# UWB_F4_MCU.net
KiCad netlist of a schematic drawn in Altium Designer
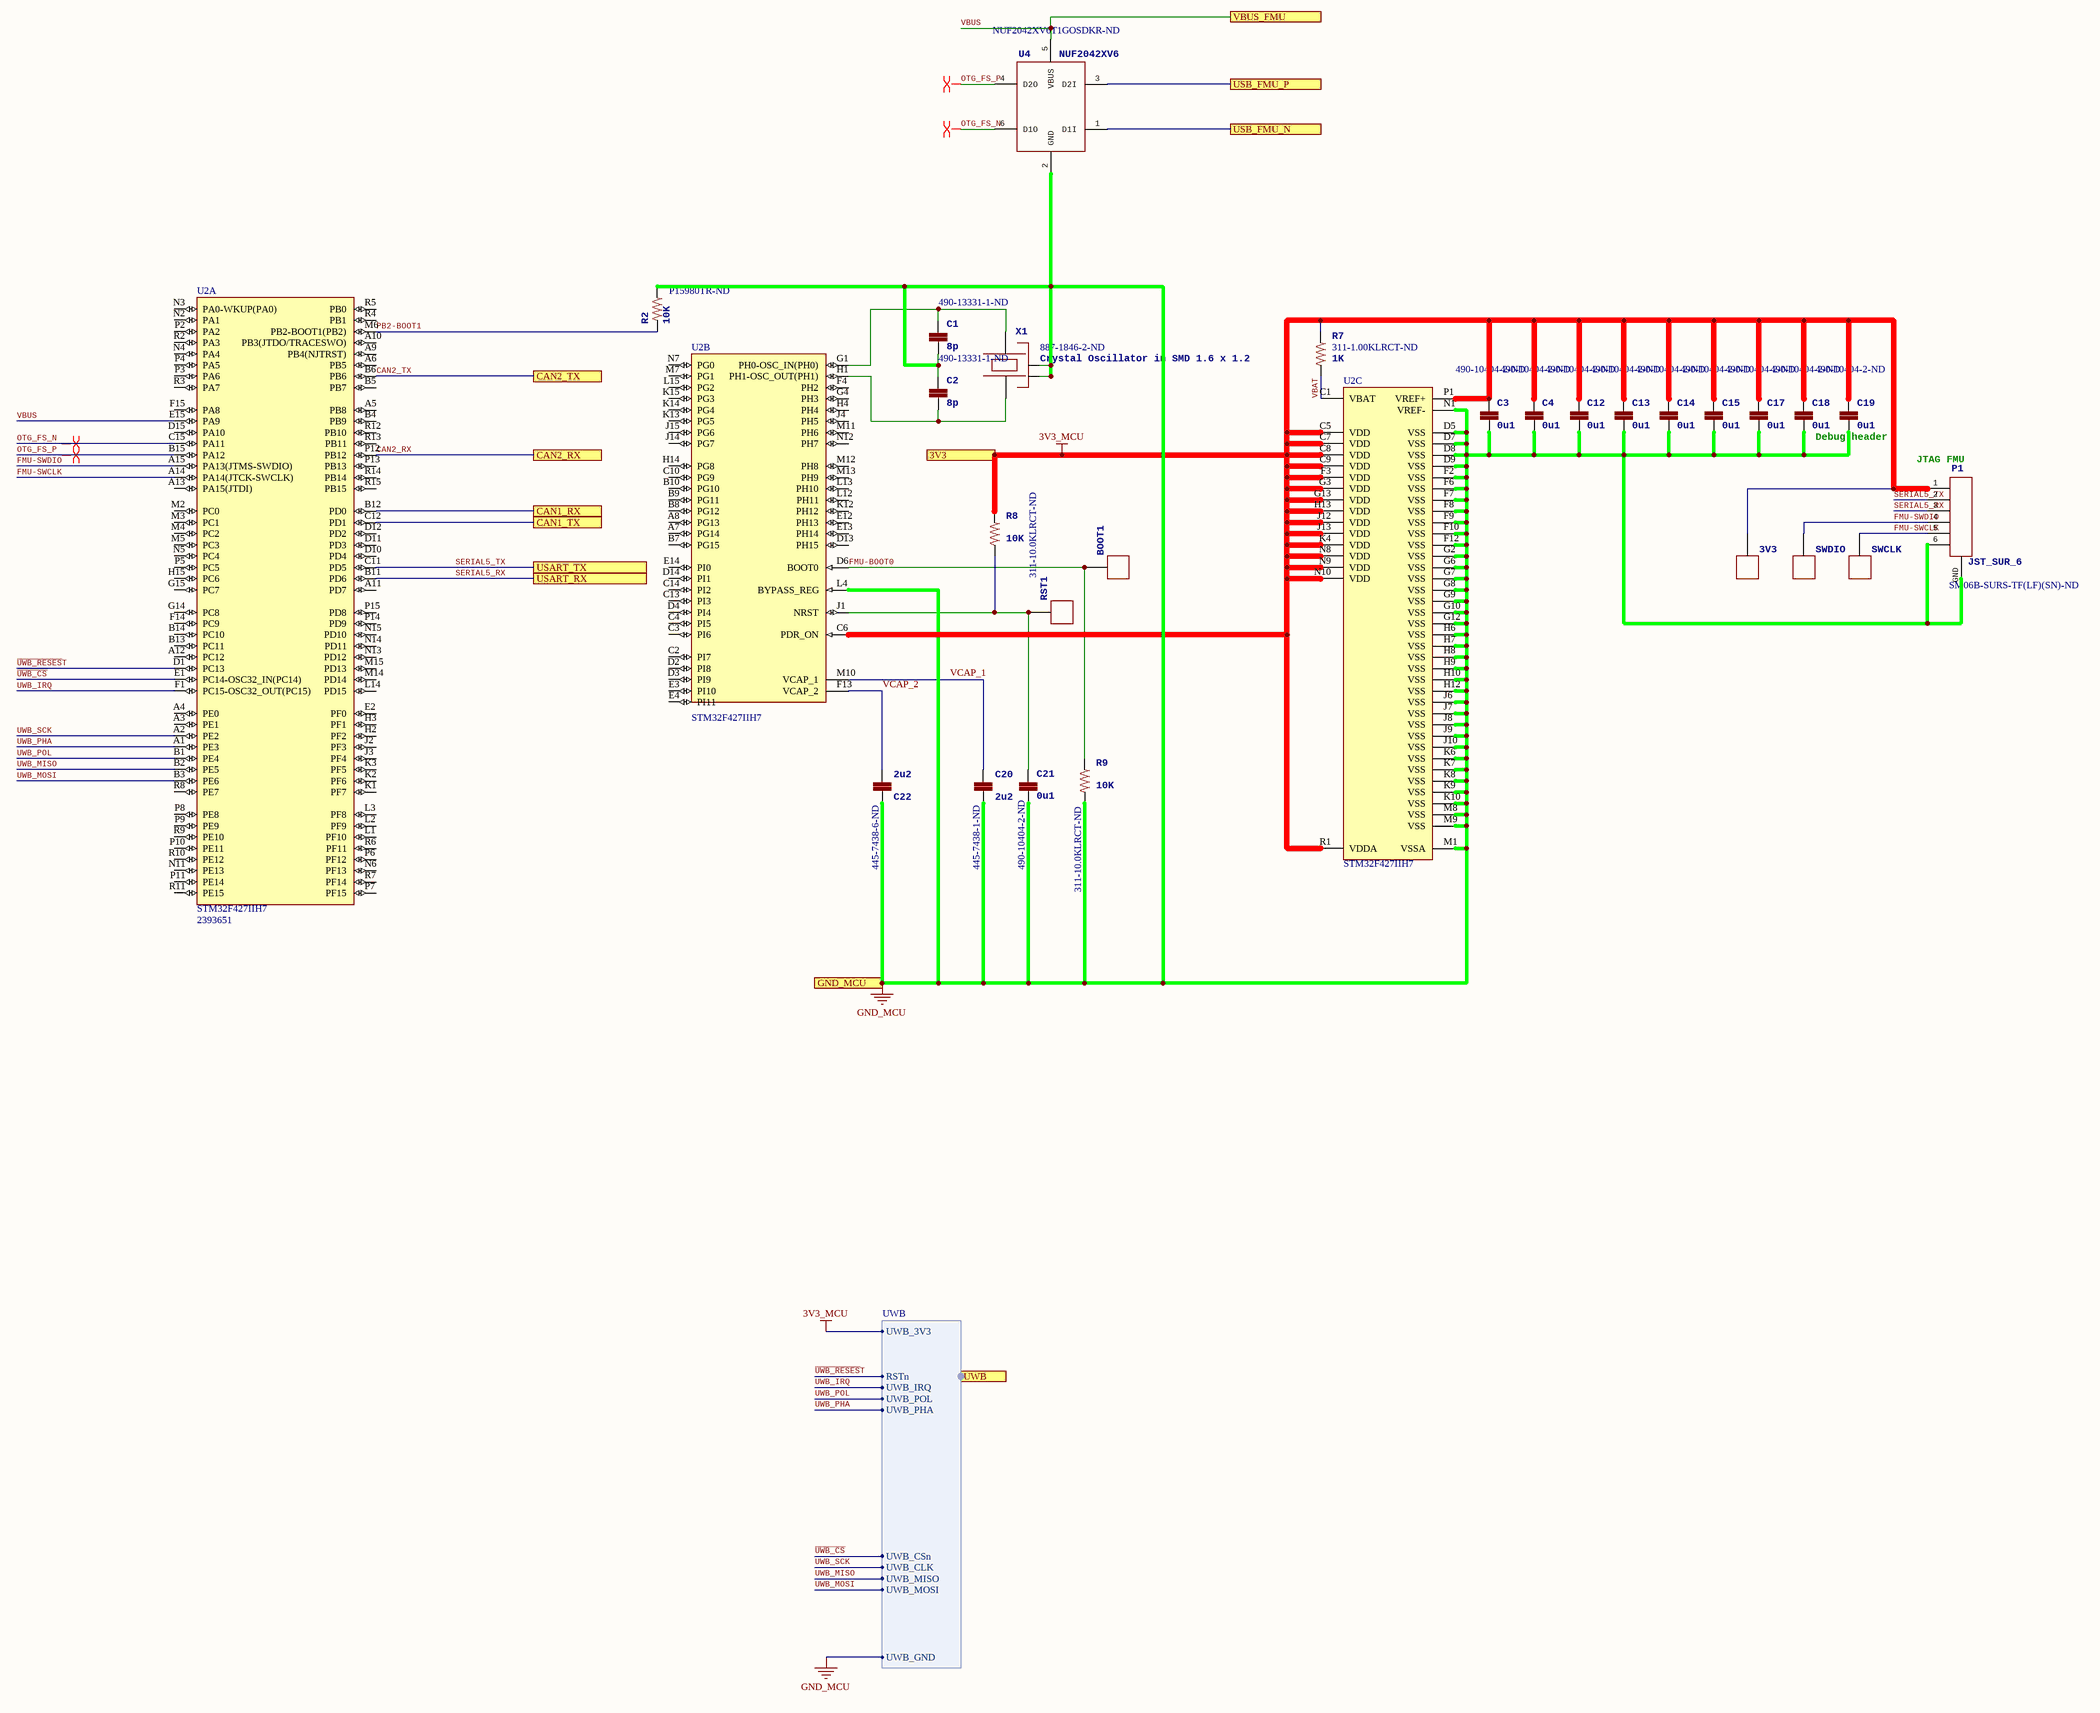
[diagram p0: UWB_F4_MCU.SchDoc]

(export (version "E")
  (design (tool "Eeschema 10.0.6"))
  (components
    (comp (ref "3V3") (value "~") (footprint "PAD.04X.04") (libsource (lib "pixhawk2") (part "PAD.04")))
    (comp (ref "BOOT1") (value "~") (footprint "PAD.04X.04") (libsource (lib "pixhawk2") (part "PAD.04")))
    (comp (ref "C1")
      (value "8p")
      (footprint "0201-cap")
      (description "CAP CER 8PF 50V NP0 0201")
      (fields (field (name "SUPPLIER PART NUMBER 1") "490-13331-1-ND"))
      (libsource (lib "altium-import") (part "root_0_CAP0402_"))
    )
    (comp (ref "C2")
      (value "8p")
      (footprint "0201-cap")
      (description "CAP CER 8PF 50V NP0 0201")
      (fields (field (name "SUPPLIER PART NUMBER 1") "490-13331-1-ND"))
      (libsource (lib "altium-import") (part "root_0_CAP0402_"))
    )
    (comp (ref "C3")
      (value "0u1")
      (footprint "0201-cap")
      (description "CAP CER 0.1UF 6V Y5V 0201")
      (fields (field (name "SUPPLIER PART NUMBER 1") "490-10404-2-ND"))
      (libsource (lib "altium-import") (part "root_0_CAP0402_"))
    )
    (comp (ref "C4")
      (value "0u1")
      (footprint "0201-cap")
      (description "CAP CER 0.1UF 6V Y5V 0201")
      (fields (field (name "SUPPLIER PART NUMBER 1") "490-10404-2-ND"))
      (libsource (lib "altium-import") (part "root_0_CAP0402_"))
    )
    (comp (ref "C12")
      (value "0u1")
      (footprint "0201-cap")
      (description "CAP CER 0.1UF 6V Y5V 0201")
      (fields (field (name "SUPPLIER PART NUMBER 1") "490-10404-2-ND"))
      (libsource (lib "altium-import") (part "root_0_CAP0402_"))
    )
    (comp (ref "C13")
      (value "0u1")
      (footprint "0201-cap")
      (description "CAP CER 0.1UF 6V Y5V 0201")
      (fields (field (name "SUPPLIER PART NUMBER 1") "490-10404-2-ND"))
      (libsource (lib "altium-import") (part "root_0_CAP0402_"))
    )
    (comp (ref "C14")
      (value "0u1")
      (footprint "0201-cap")
      (description "CAP CER 0.1UF 6V Y5V 0201")
      (fields (field (name "SUPPLIER PART NUMBER 1") "490-10404-2-ND"))
      (libsource (lib "altium-import") (part "root_0_CAP0402_"))
    )
    (comp (ref "C15")
      (value "0u1")
      (footprint "0201-cap")
      (description "CAP CER 0.1UF 6V Y5V 0201")
      (fields (field (name "SUPPLIER PART NUMBER 1") "490-10404-2-ND"))
      (libsource (lib "altium-import") (part "root_0_CAP0402_"))
    )
    (comp (ref "C17")
      (value "0u1")
      (footprint "0201-cap")
      (description "CAP CER 0.1UF 6V Y5V 0201")
      (fields (field (name "SUPPLIER PART NUMBER 1") "490-10404-2-ND"))
      (libsource (lib "altium-import") (part "root_0_CAP0402_"))
    )
    (comp (ref "C18")
      (value "0u1")
      (footprint "0201-cap")
      (description "CAP CER 0.1UF 6V Y5V 0201")
      (fields (field (name "SUPPLIER PART NUMBER 1") "490-10404-2-ND"))
      (libsource (lib "altium-import") (part "root_0_CAP0402_"))
    )
    (comp (ref "C19")
      (value "0u1")
      (footprint "0201-cap")
      (description "CAP CER 0.1UF 6V Y5V 0201")
      (fields (field (name "SUPPLIER PART NUMBER 1") "490-10404-2-ND"))
      (libsource (lib "altium-import") (part "root_0_CAP0402_"))
    )
    (comp (ref "C20")
      (value "2u2")
      (footprint "0603-CAP")
      (fields (field (name "SUPPLIER PART NUMBER 1") "445-7438-1-ND"))
      (libsource (lib "altium-import") (part "root_0_CAP0603_"))
    )
    (comp (ref "C21")
      (value "0u1")
      (footprint "0201-cap")
      (description "CAP CER 0.1UF 6V Y5V 0201")
      (fields (field (name "SUPPLIER PART NUMBER 1") "490-10404-2-ND"))
      (libsource (lib "altium-import") (part "root_0_CAP0402_"))
    )
    (comp (ref "C22")
      (value "2u2")
      (footprint "0603-CAP")
      (fields (field (name "SUPPLIER PART NUMBER 1") "445-7438-6-ND"))
      (libsource (lib "altium-import") (part "root_2_CAP0603_"))
    )
    (comp (ref "P1")
      (value "JST_SUR_6")
      (footprint "JST_SUR_H6")
      (description "Connector, Header, 6Pos, .8mm IDC, R/A, SMD, Tin")
      (fields (field (name "SUPPLIER PART NUMBER 1") "SM06B-SURS-TF(LF)(SN)-ND"))
      (libsource (lib "CB_SCI_AERO") (part "JST_SUR_6"))
    )
    (comp (ref "R2")
      (value "10K")
      (footprint "0201-RES")
      (description "RES 10K OHM 1% 0201 SMD")
      (fields (field (name "SUPPLIER PART NUMBER 1") "P15980TR-ND"))
      (libsource (lib "altium-import") (part "root_1_RESISTOR0402-RES_"))
    )
    (comp (ref "R7")
      (value "1K")
      (footprint "0402-RES")
      (fields (field (name "SUPPLIER PART NUMBER 1") "311-1.00KLRCT-ND"))
      (libsource (lib "altium-import") (part "root_1_RESISTOR0402-RES_"))
    )
    (comp (ref "R8")
      (value "10K")
      (footprint "0402-RES")
      (fields (field (name "SUPPLIER PART NUMBER 1") "311-10.0KLRCT-ND"))
      (libsource (lib "altium-import") (part "root_1_RESISTOR0402-RES_"))
    )
    (comp (ref "R9")
      (value "10K")
      (footprint "0402-RES")
      (fields (field (name "SUPPLIER PART NUMBER 1") "311-10.0KLRCT-ND"))
      (libsource (lib "altium-import") (part "root_1_RESISTOR0402-RES_"))
    )
    (comp (ref "RST1") (value "~") (footprint "PAD.04X.04") (libsource (lib "pixhawk2") (part "PAD.04")))
    (comp (ref "SWCLK") (value "~") (footprint "PAD.04X.04") (libsource (lib "pixhawk2") (part "PAD.04")))
    (comp (ref "SWDIO") (value "~") (footprint "PAD.04X.04") (libsource (lib "pixhawk2") (part "PAD.04")))
    (comp (ref "U2")
      (value "STM32F427IIH7")
      (footprint "STM-UFBGA176+25")
      (fields (field (name "SUPPLIER PART NUMBER 1") "2393651"))
      (libsource (lib "") (part "root_0_STM32F427IIH7__1"))
    )
    (comp (ref "U4")
      (value "NUF2042XV6")
      (footprint "SOT563-6")
      (description "IC FILTER USB ESD PROTECT SOT363")
      (fields (field (name "SUPPLIER PART NUMBER 1") "NUF2042XV6T1GOSDKR-ND"))
      (libsource (lib "altium-import") (part "root_0_NUF2042XV6_"))
    )
    (comp (ref "X1")
      (value "Crystal Oscillator in SMD 1.6 x 1.2")
      (footprint "OSCILLATOR-1.6x1.2")
      (description "CRYSTAL 24MHZ 8PF SMD")
      (fields (field (name "SUPPLIER PART NUMBER 1") "887-1846-2-ND"))
      (libsource (lib "altium-import") (part "root_0_OSCILLATOR-3.2X2.5_"))
    )
  )
  (nets
    (net (code "2") (name "/CAN1_RX") (class "Default")
      (node (ref "U2") (pin "B12") (pinfunction "PD0_B12") (pintype "bidirectional"))
    )
    (net (code "3") (name "/CAN1_TX") (class "Default")
      (node (ref "U2") (pin "C12") (pinfunction "PD1_C12") (pintype "bidirectional"))
    )
    (net (code "4") (name "/CAN2_RX") (class "Default")
      (node (ref "U2") (pin "P12") (pinfunction "PB12_P12") (pintype "bidirectional"))
    )
    (net (code "5") (name "/CAN2_TX") (class "Default")
      (node (ref "U2") (pin "B6") (pinfunction "PB6_B6") (pintype "bidirectional"))
    )
    (net (code "6") (name "/FMU-BOOT0") (class "Default")
      (node (ref "BOOT1") (pin "1") (pinfunction "1_1") (pintype "passive"))
      (node (ref "R9") (pin "2") (pinfunction "2_2") (pintype "passive"))
      (node (ref "U2") (pin "D6") (pinfunction "BOOT0_D6") (pintype "input"))
    )
    (net (code "7") (name "/FMU-SWCLK") (class "Default")
      (node (ref "P1") (pin "5") (pinfunction "5_5") (pintype "passive"))
      (node (ref "SWCLK") (pin "1") (pinfunction "1_1") (pintype "passive"))
      (node (ref "U2") (pin "A14") (pinfunction "PA14(JTCK-SWCLK)_A14") (pintype "bidirectional"))
    )
    (net (code "8") (name "/FMU-SWDIO") (class "Default")
      (node (ref "P1") (pin "4") (pinfunction "4_4") (pintype "passive"))
      (node (ref "SWDIO") (pin "1") (pinfunction "1_1") (pintype "passive"))
      (node (ref "U2") (pin "A15") (pinfunction "PA13(JTMS-SWDIO)_A15") (pintype "bidirectional"))
    )
    (net (code "9") (name "/OTG_FS_N") (class "Default")
      (node (ref "U2") (pin "C15") (pinfunction "PA11_C15") (pintype "bidirectional"))
      (node (ref "U4") (pin "6") (pinfunction "D1O_6") (pintype "passive"))
    )
    (net (code "10") (name "/OTG_FS_P") (class "Default")
      (node (ref "U2") (pin "B15") (pinfunction "PA12_B15") (pintype "bidirectional"))
      (node (ref "U4") (pin "4") (pinfunction "D2O_4") (pintype "passive"))
    )
    (net (code "11") (name "/PB2-BOOT1") (class "Default")
      (node (ref "R2") (pin "1") (pinfunction "1_1") (pintype "passive"))
      (node (ref "U2") (pin "M6") (pinfunction "PB2-BOOT1(PB2)_M6") (pintype "bidirectional"))
    )
    (net (code "12") (name "/SERIAL5_RX") (class "Default")
      (node (ref "P1") (pin "3") (pinfunction "3_3") (pintype "passive"))
      (node (ref "U2") (pin "B11") (pinfunction "PD6_B11") (pintype "bidirectional"))
    )
    (net (code "13") (name "/SERIAL5_TX") (class "Default")
      (node (ref "P1") (pin "2") (pinfunction "2_2") (pintype "passive"))
      (node (ref "U2") (pin "C11") (pinfunction "PD5_C11") (pintype "bidirectional"))
    )
    (net (code "14") (name "/USB_FMU_N") (class "Default")
      (node (ref "U4") (pin "1") (pinfunction "D1I_1") (pintype "passive"))
    )
    (net (code "15") (name "/USB_FMU_P") (class "Default")
      (node (ref "U4") (pin "3") (pinfunction "D2I_3") (pintype "passive"))
    )
    (net (code "16") (name "/UWB_IRQ") (class "Default")
      (node (ref "U2") (pin "F1") (pinfunction "PC15-OSC32_OUT(PC15)_F1") (pintype "bidirectional"))
    )
    (net (code "17") (name "/UWB_MISO") (class "Default")
      (node (ref "U2") (pin "B2") (pinfunction "PE5_B2") (pintype "bidirectional"))
    )
    (net (code "18") (name "/UWB_MOSI") (class "Default")
      (node (ref "U2") (pin "B3") (pinfunction "PE6_B3") (pintype "bidirectional"))
    )
    (net (code "19") (name "/UWB_PHA") (class "Default")
      (node (ref "U2") (pin "A1") (pinfunction "PE3_A1") (pintype "bidirectional"))
    )
    (net (code "20") (name "/UWB_POL") (class "Default")
      (node (ref "U2") (pin "B1") (pinfunction "PE4_B1") (pintype "bidirectional"))
    )
    (net (code "21") (name "/UWB_SCK") (class "Default")
      (node (ref "U2") (pin "A2") (pinfunction "PE2_A2") (pintype "bidirectional"))
    )
    (net (code "22") (name "/VBAT") (class "Default")
      (node (ref "R7") (pin "1") (pinfunction "1_1") (pintype "passive"))
      (node (ref "U2") (pin "C1") (pinfunction "VBAT_C1") (pintype "power_in"))
    )
    (net (code "23") (name "/VBUS") (class "Default")
      (node (ref "U2") (pin "E15") (pinfunction "PA9_E15") (pintype "bidirectional"))
      (node (ref "U4") (pin "5") (pinfunction "VBUS_5") (pintype "passive"))
    )
    (net (code "24") (name "/VCAP_1") (class "Default")
      (node (ref "C20") (pin "1") (pinfunction "1_1") (pintype "passive"))
      (node (ref "U2") (pin "M10") (pinfunction "VCAP_1_M10") (pintype "power_in"))
    )
    (net (code "25") (name "/VCAP_2") (class "Default")
      (node (ref "C22") (pin "2") (pinfunction "2_2") (pintype "passive"))
      (node (ref "U2") (pin "F13") (pinfunction "VCAP_2_F13") (pintype "power_in"))
    )
    (net (code "27") (name "/~{UWB_CS}") (class "Default")
      (node (ref "U2") (pin "E1") (pinfunction "PC14-OSC32_IN(PC14)_E1") (pintype "bidirectional"))
    )
    (net (code "28") (name "/~{UWB_RESES}T") (class "Default")
      (node (ref "U2") (pin "D1") (pinfunction "PC13_D1") (pintype "bidirectional"))
    )
    (net (code "29") (name "3V3_MCU") (class "Default")
      (node (ref "3V3") (pin "1") (pinfunction "1_1") (pintype "passive"))
      (node (ref "C12") (pin "1") (pinfunction "1_1") (pintype "passive"))
      (node (ref "C13") (pin "1") (pinfunction "1_1") (pintype "passive"))
      (node (ref "C14") (pin "1") (pinfunction "1_1") (pintype "passive"))
      (node (ref "C15") (pin "1") (pinfunction "1_1") (pintype "passive"))
      (node (ref "C17") (pin "1") (pinfunction "1_1") (pintype "passive"))
      (node (ref "C18") (pin "1") (pinfunction "1_1") (pintype "passive"))
      (node (ref "C19") (pin "1") (pinfunction "1_1") (pintype "passive"))
      (node (ref "C3") (pin "1") (pinfunction "1_1") (pintype "passive"))
      (node (ref "C4") (pin "1") (pinfunction "1_1") (pintype "passive"))
      (node (ref "P1") (pin "1") (pinfunction "1_1") (pintype "passive"))
      (node (ref "R7") (pin "2") (pinfunction "2_2") (pintype "passive"))
      (node (ref "R8") (pin "2") (pinfunction "2_2") (pintype "passive"))
      (node (ref "U2") (pin "C5") (pinfunction "VDD_C5") (pintype "power_in"))
      (node (ref "U2") (pin "C6") (pinfunction "PDR_ON_C6") (pintype "input"))
      (node (ref "U2") (pin "C7") (pinfunction "VDD_C7") (pintype "power_in"))
      (node (ref "U2") (pin "C8") (pinfunction "VDD_C8") (pintype "power_in"))
      (node (ref "U2") (pin "C9") (pinfunction "VDD_C9") (pintype "power_in"))
      (node (ref "U2") (pin "F3") (pinfunction "VDD_F3") (pintype "power_in"))
      (node (ref "U2") (pin "G13") (pinfunction "VDD_G13") (pintype "power_in"))
      (node (ref "U2") (pin "G3") (pinfunction "VDD_G3") (pintype "power_in"))
      (node (ref "U2") (pin "H13") (pinfunction "VDD_H13") (pintype "power_in"))
      (node (ref "U2") (pin "J12") (pinfunction "VDD_J12") (pintype "power_in"))
      (node (ref "U2") (pin "J13") (pinfunction "VDD_J13") (pintype "power_in"))
      (node (ref "U2") (pin "K4") (pinfunction "VDD_K4") (pintype "power_in"))
      (node (ref "U2") (pin "N10") (pinfunction "VDD_N10") (pintype "power_in"))
      (node (ref "U2") (pin "N8") (pinfunction "VDD_N8") (pintype "power_in"))
      (node (ref "U2") (pin "N9") (pinfunction "VDD_N9") (pintype "power_in"))
      (node (ref "U2") (pin "P1") (pinfunction "VREF+_P1") (pintype "power_in"))
      (node (ref "U2") (pin "R1") (pinfunction "VDDA_R1") (pintype "power_in"))
    )
    (net (code "30") (name "GND_MCU") (class "Default")
      (node (ref "C1") (pin "2") (pinfunction "2_2") (pintype "passive"))
      (node (ref "C12") (pin "2") (pinfunction "2_2") (pintype "passive"))
      (node (ref "C13") (pin "2") (pinfunction "2_2") (pintype "passive"))
      (node (ref "C14") (pin "2") (pinfunction "2_2") (pintype "passive"))
      (node (ref "C15") (pin "2") (pinfunction "2_2") (pintype "passive"))
      (node (ref "C17") (pin "2") (pinfunction "2_2") (pintype "passive"))
      (node (ref "C18") (pin "2") (pinfunction "2_2") (pintype "passive"))
      (node (ref "C19") (pin "2") (pinfunction "2_2") (pintype "passive"))
      (node (ref "C2") (pin "1") (pinfunction "1_1") (pintype "passive"))
      (node (ref "C20") (pin "2") (pinfunction "2_2") (pintype "passive"))
      (node (ref "C21") (pin "2") (pinfunction "2_2") (pintype "passive"))
      (node (ref "C22") (pin "1") (pinfunction "1_1") (pintype "passive"))
      (node (ref "C3") (pin "2") (pinfunction "2_2") (pintype "passive"))
      (node (ref "C4") (pin "2") (pinfunction "2_2") (pintype "passive"))
      (node (ref "P1") (pin "6") (pinfunction "6_6") (pintype "passive"))
      (node (ref "P1") (pin "GND") (pinfunction "GND_GND") (pintype "passive"))
      (node (ref "R2") (pin "2") (pinfunction "2_2") (pintype "passive"))
      (node (ref "R9") (pin "1") (pinfunction "1_1") (pintype "passive"))
      (node (ref "U2") (pin "D5") (pinfunction "VSS_D5") (pintype "power_in"))
      (node (ref "U2") (pin "D7") (pinfunction "VSS_D7") (pintype "power_in"))
      (node (ref "U2") (pin "D8") (pinfunction "VSS_D8") (pintype "power_in"))
      (node (ref "U2") (pin "D9") (pinfunction "VSS_D9") (pintype "power_in"))
      (node (ref "U2") (pin "F10") (pinfunction "VSS_F10") (pintype "power_in"))
      (node (ref "U2") (pin "F12") (pinfunction "VSS_F12") (pintype "power_in"))
      (node (ref "U2") (pin "F2") (pinfunction "VSS_F2") (pintype "power_in"))
      (node (ref "U2") (pin "F6") (pinfunction "VSS_F6") (pintype "power_in"))
      (node (ref "U2") (pin "F7") (pinfunction "VSS_F7") (pintype "power_in"))
      (node (ref "U2") (pin "F8") (pinfunction "VSS_F8") (pintype "power_in"))
      (node (ref "U2") (pin "F9") (pinfunction "VSS_F9") (pintype "power_in"))
      (node (ref "U2") (pin "G10") (pinfunction "VSS_G10") (pintype "power_in"))
      (node (ref "U2") (pin "G12") (pinfunction "VSS_G12") (pintype "power_in"))
      (node (ref "U2") (pin "G2") (pinfunction "VSS_G2") (pintype "power_in"))
      (node (ref "U2") (pin "G6") (pinfunction "VSS_G6") (pintype "power_in"))
      (node (ref "U2") (pin "G7") (pinfunction "VSS_G7") (pintype "power_in"))
      (node (ref "U2") (pin "G8") (pinfunction "VSS_G8") (pintype "power_in"))
      (node (ref "U2") (pin "G9") (pinfunction "VSS_G9") (pintype "power_in"))
      (node (ref "U2") (pin "H10") (pinfunction "VSS_H10") (pintype "power_in"))
      (node (ref "U2") (pin "H12") (pinfunction "VSS_H12") (pintype "power_in"))
      (node (ref "U2") (pin "H6") (pinfunction "VSS_H6") (pintype "power_in"))
      (node (ref "U2") (pin "H7") (pinfunction "VSS_H7") (pintype "power_in"))
      (node (ref "U2") (pin "H8") (pinfunction "VSS_H8") (pintype "power_in"))
      (node (ref "U2") (pin "H9") (pinfunction "VSS_H9") (pintype "power_in"))
      (node (ref "U2") (pin "J10") (pinfunction "VSS_J10") (pintype "power_in"))
      (node (ref "U2") (pin "J6") (pinfunction "VSS_J6") (pintype "power_in"))
      (node (ref "U2") (pin "J7") (pinfunction "VSS_J7") (pintype "power_in"))
      (node (ref "U2") (pin "J8") (pinfunction "VSS_J8") (pintype "power_in"))
      (node (ref "U2") (pin "J9") (pinfunction "VSS_J9") (pintype "power_in"))
      (node (ref "U2") (pin "K10") (pinfunction "VSS_K10") (pintype "power_in"))
      (node (ref "U2") (pin "K6") (pinfunction "VSS_K6") (pintype "power_in"))
      (node (ref "U2") (pin "K7") (pinfunction "VSS_K7") (pintype "power_in"))
      (node (ref "U2") (pin "K8") (pinfunction "VSS_K8") (pintype "power_in"))
      (node (ref "U2") (pin "K9") (pinfunction "VSS_K9") (pintype "power_in"))
      (node (ref "U2") (pin "L4") (pinfunction "BYPASS_REG_L4") (pintype "input"))
      (node (ref "U2") (pin "M1") (pinfunction "VSSA_M1") (pintype "power_in"))
      (node (ref "U2") (pin "M8") (pinfunction "VSS_M8") (pintype "power_in"))
      (node (ref "U2") (pin "M9") (pinfunction "VSS_M9") (pintype "power_in"))
      (node (ref "U2") (pin "N1") (pinfunction "VREF-_N1") (pintype "power_in"))
      (node (ref "U4") (pin "2") (pinfunction "GND_2") (pintype "passive"))
      (node (ref "X1") (pin "2") (pinfunction "NC_2_2") (pintype "passive"))
      (node (ref "X1") (pin "4") (pinfunction "NC_4_4") (pintype "passive"))
    )
    (net (code "31") (name "Net-(U2B-NRST)") (class "Default")
      (node (ref "C21") (pin "1") (pinfunction "1_1") (pintype "passive"))
      (node (ref "R8") (pin "1") (pinfunction "1_1") (pintype "passive"))
      (node (ref "RST1") (pin "1") (pinfunction "1_1") (pintype "passive"))
      (node (ref "U2") (pin "J1") (pinfunction "NRST_J1") (pintype "bidirectional"))
    )
    (net (code "32") (name "Net-(U2B-PH0-OSC_IN(PH0))") (class "Default")
      (node (ref "C1") (pin "1") (pinfunction "1_1") (pintype "passive"))
      (node (ref "U2") (pin "G1") (pinfunction "PH0-OSC_IN(PH0)_G1") (pintype "bidirectional"))
      (node (ref "X1") (pin "3") (pinfunction "3_3") (pintype "passive"))
    )
    (net (code "33") (name "Net-(U2B-PH1-OSC_OUT(PH1))") (class "Default")
      (node (ref "C2") (pin "2") (pinfunction "2_2") (pintype "passive"))
      (node (ref "U2") (pin "H1") (pinfunction "PH1-OSC_OUT(PH1)_H1") (pintype "bidirectional"))
      (node (ref "X1") (pin "1") (pinfunction "1_1") (pintype "passive"))
    )
    (net (code "34") (name "unconnected-(U2A-PA0-WKUP(PA0)-PadN3)") (class "Default")
      (node (ref "U2") (pin "N3") (pinfunction "PA0-WKUP(PA0)_N3") (pintype "bidirectional"))
    )
    (net (code "35") (name "unconnected-(U2A-PA1-PadN2)") (class "Default")
      (node (ref "U2") (pin "N2") (pinfunction "PA1_N2") (pintype "bidirectional"))
    )
    (net (code "36") (name "unconnected-(U2A-PA2-PadP2)") (class "Default")
      (node (ref "U2") (pin "P2") (pinfunction "PA2_P2") (pintype "bidirectional"))
    )
    (net (code "37") (name "unconnected-(U2A-PA3-PadR2)") (class "Default")
      (node (ref "U2") (pin "R2") (pinfunction "PA3_R2") (pintype "bidirectional"))
    )
    (net (code "38") (name "unconnected-(U2A-PA4-PadN4)") (class "Default")
      (node (ref "U2") (pin "N4") (pinfunction "PA4_N4") (pintype "bidirectional"))
    )
    (net (code "39") (name "unconnected-(U2A-PA5-PadP4)") (class "Default")
      (node (ref "U2") (pin "P4") (pinfunction "PA5_P4") (pintype "bidirectional"))
    )
    (net (code "40") (name "unconnected-(U2A-PA6-PadP3)") (class "Default")
      (node (ref "U2") (pin "P3") (pinfunction "PA6_P3") (pintype "bidirectional"))
    )
    (net (code "41") (name "unconnected-(U2A-PA7-PadR3)") (class "Default")
      (node (ref "U2") (pin "R3") (pinfunction "PA7_R3") (pintype "bidirectional"))
    )
    (net (code "42") (name "unconnected-(U2A-PA8-PadF15)") (class "Default")
      (node (ref "U2") (pin "F15") (pinfunction "PA8_F15") (pintype "bidirectional"))
    )
    (net (code "43") (name "unconnected-(U2A-PA10-PadD15)") (class "Default")
      (node (ref "U2") (pin "D15") (pinfunction "PA10_D15") (pintype "bidirectional"))
    )
    (net (code "44") (name "unconnected-(U2A-PA15(JTDI)-PadA13)") (class "Default")
      (node (ref "U2") (pin "A13") (pinfunction "PA15(JTDI)_A13") (pintype "bidirectional"))
    )
    (net (code "45") (name "unconnected-(U2A-PB0-PadR5)") (class "Default")
      (node (ref "U2") (pin "R5") (pinfunction "PB0_R5") (pintype "bidirectional"))
    )
    (net (code "46") (name "unconnected-(U2A-PB1-PadR4)") (class "Default")
      (node (ref "U2") (pin "R4") (pinfunction "PB1_R4") (pintype "bidirectional"))
    )
    (net (code "47") (name "unconnected-(U2A-PB3(JTDO{slash}TRACESWO)-PadA10)") (class "Default")
      (node (ref "U2") (pin "A10") (pinfunction "PB3(JTDO/TRACESWO)_A10") (pintype "bidirectional"))
    )
    (net (code "48") (name "unconnected-(U2A-PB4(NJTRST)-PadA9)") (class "Default")
      (node (ref "U2") (pin "A9") (pinfunction "PB4(NJTRST)_A9") (pintype "bidirectional"))
    )
    (net (code "49") (name "unconnected-(U2A-PB5-PadA6)") (class "Default")
      (node (ref "U2") (pin "A6") (pinfunction "PB5_A6") (pintype "bidirectional"))
    )
    (net (code "50") (name "unconnected-(U2A-PB7-PadB5)") (class "Default")
      (node (ref "U2") (pin "B5") (pinfunction "PB7_B5") (pintype "bidirectional"))
    )
    (net (code "51") (name "unconnected-(U2A-PB8-PadA5)") (class "Default")
      (node (ref "U2") (pin "A5") (pinfunction "PB8_A5") (pintype "bidirectional"))
    )
    (net (code "52") (name "unconnected-(U2A-PB9-PadB4)") (class "Default")
      (node (ref "U2") (pin "B4") (pinfunction "PB9_B4") (pintype "bidirectional"))
    )
    (net (code "53") (name "unconnected-(U2A-PB10-PadR12)") (class "Default")
      (node (ref "U2") (pin "R12") (pinfunction "PB10_R12") (pintype "bidirectional"))
    )
    (net (code "54") (name "unconnected-(U2A-PB11-PadR13)") (class "Default")
      (node (ref "U2") (pin "R13") (pinfunction "PB11_R13") (pintype "bidirectional"))
    )
    (net (code "55") (name "unconnected-(U2A-PB13-PadP13)") (class "Default")
      (node (ref "U2") (pin "P13") (pinfunction "PB13_P13") (pintype "bidirectional"))
    )
    (net (code "56") (name "unconnected-(U2A-PB14-PadR14)") (class "Default")
      (node (ref "U2") (pin "R14") (pinfunction "PB14_R14") (pintype "bidirectional"))
    )
    (net (code "57") (name "unconnected-(U2A-PB15-PadR15)") (class "Default")
      (node (ref "U2") (pin "R15") (pinfunction "PB15_R15") (pintype "bidirectional"))
    )
    (net (code "58") (name "unconnected-(U2A-PC0-PadM2)") (class "Default")
      (node (ref "U2") (pin "M2") (pinfunction "PC0_M2") (pintype "bidirectional"))
    )
    (net (code "59") (name "unconnected-(U2A-PC1-PadM3)") (class "Default")
      (node (ref "U2") (pin "M3") (pinfunction "PC1_M3") (pintype "bidirectional"))
    )
    (net (code "60") (name "unconnected-(U2A-PC2-PadM4)") (class "Default")
      (node (ref "U2") (pin "M4") (pinfunction "PC2_M4") (pintype "bidirectional"))
    )
    (net (code "61") (name "unconnected-(U2A-PC3-PadM5)") (class "Default")
      (node (ref "U2") (pin "M5") (pinfunction "PC3_M5") (pintype "bidirectional"))
    )
    (net (code "62") (name "unconnected-(U2A-PC4-PadN5)") (class "Default")
      (node (ref "U2") (pin "N5") (pinfunction "PC4_N5") (pintype "bidirectional"))
    )
    (net (code "63") (name "unconnected-(U2A-PC5-PadP5)") (class "Default")
      (node (ref "U2") (pin "P5") (pinfunction "PC5_P5") (pintype "bidirectional"))
    )
    (net (code "64") (name "unconnected-(U2A-PC6-PadH15)") (class "Default")
      (node (ref "U2") (pin "H15") (pinfunction "PC6_H15") (pintype "bidirectional"))
    )
    (net (code "65") (name "unconnected-(U2A-PC7-PadG15)") (class "Default")
      (node (ref "U2") (pin "G15") (pinfunction "PC7_G15") (pintype "bidirectional"))
    )
    (net (code "66") (name "unconnected-(U2A-PC8-PadG14)") (class "Default")
      (node (ref "U2") (pin "G14") (pinfunction "PC8_G14") (pintype "bidirectional"))
    )
    (net (code "67") (name "unconnected-(U2A-PC9-PadF14)") (class "Default")
      (node (ref "U2") (pin "F14") (pinfunction "PC9_F14") (pintype "bidirectional"))
    )
    (net (code "68") (name "unconnected-(U2A-PC10-PadB14)") (class "Default")
      (node (ref "U2") (pin "B14") (pinfunction "PC10_B14") (pintype "bidirectional"))
    )
    (net (code "69") (name "unconnected-(U2A-PC11-PadB13)") (class "Default")
      (node (ref "U2") (pin "B13") (pinfunction "PC11_B13") (pintype "bidirectional"))
    )
    (net (code "70") (name "unconnected-(U2A-PC12-PadA12)") (class "Default")
      (node (ref "U2") (pin "A12") (pinfunction "PC12_A12") (pintype "bidirectional"))
    )
    (net (code "71") (name "unconnected-(U2A-PD2-PadD12)") (class "Default")
      (node (ref "U2") (pin "D12") (pinfunction "PD2_D12") (pintype "bidirectional"))
    )
    (net (code "72") (name "unconnected-(U2A-PD3-PadD11)") (class "Default")
      (node (ref "U2") (pin "D11") (pinfunction "PD3_D11") (pintype "bidirectional"))
    )
    (net (code "73") (name "unconnected-(U2A-PD4-PadD10)") (class "Default")
      (node (ref "U2") (pin "D10") (pinfunction "PD4_D10") (pintype "bidirectional"))
    )
    (net (code "74") (name "unconnected-(U2A-PD7-PadA11)") (class "Default")
      (node (ref "U2") (pin "A11") (pinfunction "PD7_A11") (pintype "bidirectional"))
    )
    (net (code "75") (name "unconnected-(U2A-PD8-PadP15)") (class "Default")
      (node (ref "U2") (pin "P15") (pinfunction "PD8_P15") (pintype "bidirectional"))
    )
    (net (code "76") (name "unconnected-(U2A-PD9-PadP14)") (class "Default")
      (node (ref "U2") (pin "P14") (pinfunction "PD9_P14") (pintype "bidirectional"))
    )
    (net (code "77") (name "unconnected-(U2A-PD10-PadN15)") (class "Default")
      (node (ref "U2") (pin "N15") (pinfunction "PD10_N15") (pintype "bidirectional"))
    )
    (net (code "78") (name "unconnected-(U2A-PD11-PadN14)") (class "Default")
      (node (ref "U2") (pin "N14") (pinfunction "PD11_N14") (pintype "bidirectional"))
    )
    (net (code "79") (name "unconnected-(U2A-PD12-PadN13)") (class "Default")
      (node (ref "U2") (pin "N13") (pinfunction "PD12_N13") (pintype "bidirectional"))
    )
    (net (code "80") (name "unconnected-(U2A-PD13-PadM15)") (class "Default")
      (node (ref "U2") (pin "M15") (pinfunction "PD13_M15") (pintype "bidirectional"))
    )
    (net (code "81") (name "unconnected-(U2A-PD14-PadM14)") (class "Default")
      (node (ref "U2") (pin "M14") (pinfunction "PD14_M14") (pintype "bidirectional"))
    )
    (net (code "82") (name "unconnected-(U2A-PD15-PadL14)") (class "Default")
      (node (ref "U2") (pin "L14") (pinfunction "PD15_L14") (pintype "bidirectional"))
    )
    (net (code "83") (name "unconnected-(U2A-PE0-PadA4)") (class "Default")
      (node (ref "U2") (pin "A4") (pinfunction "PE0_A4") (pintype "bidirectional"))
    )
    (net (code "84") (name "unconnected-(U2A-PE1-PadA3)") (class "Default")
      (node (ref "U2") (pin "A3") (pinfunction "PE1_A3") (pintype "bidirectional"))
    )
    (net (code "85") (name "unconnected-(U2A-PE7-PadR8)") (class "Default")
      (node (ref "U2") (pin "R8") (pinfunction "PE7_R8") (pintype "bidirectional"))
    )
    (net (code "86") (name "unconnected-(U2A-PE8-PadP8)") (class "Default")
      (node (ref "U2") (pin "P8") (pinfunction "PE8_P8") (pintype "bidirectional"))
    )
    (net (code "87") (name "unconnected-(U2A-PE9-PadP9)") (class "Default")
      (node (ref "U2") (pin "P9") (pinfunction "PE9_P9") (pintype "bidirectional"))
    )
    (net (code "88") (name "unconnected-(U2A-PE10-PadR9)") (class "Default")
      (node (ref "U2") (pin "R9") (pinfunction "PE10_R9") (pintype "bidirectional"))
    )
    (net (code "89") (name "unconnected-(U2A-PE11-PadP10)") (class "Default")
      (node (ref "U2") (pin "P10") (pinfunction "PE11_P10") (pintype "bidirectional"))
    )
    (net (code "90") (name "unconnected-(U2A-PE12-PadR10)") (class "Default")
      (node (ref "U2") (pin "R10") (pinfunction "PE12_R10") (pintype "bidirectional"))
    )
    (net (code "91") (name "unconnected-(U2A-PE13-PadN11)") (class "Default")
      (node (ref "U2") (pin "N11") (pinfunction "PE13_N11") (pintype "bidirectional"))
    )
    (net (code "92") (name "unconnected-(U2A-PE14-PadP11)") (class "Default")
      (node (ref "U2") (pin "P11") (pinfunction "PE14_P11") (pintype "bidirectional"))
    )
    (net (code "93") (name "unconnected-(U2A-PE15-PadR11)") (class "Default")
      (node (ref "U2") (pin "R11") (pinfunction "PE15_R11") (pintype "bidirectional"))
    )
    (net (code "94") (name "unconnected-(U2A-PF0-PadE2)") (class "Default")
      (node (ref "U2") (pin "E2") (pinfunction "PF0_E2") (pintype "bidirectional"))
    )
    (net (code "95") (name "unconnected-(U2A-PF1-PadH3)") (class "Default")
      (node (ref "U2") (pin "H3") (pinfunction "PF1_H3") (pintype "bidirectional"))
    )
    (net (code "96") (name "unconnected-(U2A-PF2-PadH2)") (class "Default")
      (node (ref "U2") (pin "H2") (pinfunction "PF2_H2") (pintype "bidirectional"))
    )
    (net (code "97") (name "unconnected-(U2A-PF3-PadJ2)") (class "Default")
      (node (ref "U2") (pin "J2") (pinfunction "PF3_J2") (pintype "bidirectional"))
    )
    (net (code "98") (name "unconnected-(U2A-PF4-PadJ3)") (class "Default")
      (node (ref "U2") (pin "J3") (pinfunction "PF4_J3") (pintype "bidirectional"))
    )
    (net (code "99") (name "unconnected-(U2A-PF5-PadK3)") (class "Default")
      (node (ref "U2") (pin "K3") (pinfunction "PF5_K3") (pintype "bidirectional"))
    )
    (net (code "100") (name "unconnected-(U2A-PF6-PadK2)") (class "Default")
      (node (ref "U2") (pin "K2") (pinfunction "PF6_K2") (pintype "bidirectional"))
    )
    (net (code "101") (name "unconnected-(U2A-PF7-PadK1)") (class "Default")
      (node (ref "U2") (pin "K1") (pinfunction "PF7_K1") (pintype "bidirectional"))
    )
    (net (code "102") (name "unconnected-(U2A-PF8-PadL3)") (class "Default")
      (node (ref "U2") (pin "L3") (pinfunction "PF8_L3") (pintype "bidirectional"))
    )
    (net (code "103") (name "unconnected-(U2A-PF9-PadL2)") (class "Default")
      (node (ref "U2") (pin "L2") (pinfunction "PF9_L2") (pintype "bidirectional"))
    )
    (net (code "104") (name "unconnected-(U2A-PF10-PadL1)") (class "Default")
      (node (ref "U2") (pin "L1") (pinfunction "PF10_L1") (pintype "bidirectional"))
    )
    (net (code "105") (name "unconnected-(U2A-PF11-PadR6)") (class "Default")
      (node (ref "U2") (pin "R6") (pinfunction "PF11_R6") (pintype "bidirectional"))
    )
    (net (code "106") (name "unconnected-(U2A-PF12-PadP6)") (class "Default")
      (node (ref "U2") (pin "P6") (pinfunction "PF12_P6") (pintype "bidirectional"))
    )
    (net (code "107") (name "unconnected-(U2A-PF13-PadN6)") (class "Default")
      (node (ref "U2") (pin "N6") (pinfunction "PF13_N6") (pintype "bidirectional"))
    )
    (net (code "108") (name "unconnected-(U2A-PF14-PadR7)") (class "Default")
      (node (ref "U2") (pin "R7") (pinfunction "PF14_R7") (pintype "bidirectional"))
    )
    (net (code "109") (name "unconnected-(U2A-PF15-PadP7)") (class "Default")
      (node (ref "U2") (pin "P7") (pinfunction "PF15_P7") (pintype "bidirectional"))
    )
    (net (code "110") (name "unconnected-(U2B-PG0-PadN7)") (class "Default")
      (node (ref "U2") (pin "N7") (pinfunction "PG0_N7") (pintype "bidirectional"))
    )
    (net (code "111") (name "unconnected-(U2B-PG1-PadM7)") (class "Default")
      (node (ref "U2") (pin "M7") (pinfunction "PG1_M7") (pintype "bidirectional"))
    )
    (net (code "112") (name "unconnected-(U2B-PG2-PadL15)") (class "Default")
      (node (ref "U2") (pin "L15") (pinfunction "PG2_L15") (pintype "bidirectional"))
    )
    (net (code "113") (name "unconnected-(U2B-PG3-PadK15)") (class "Default")
      (node (ref "U2") (pin "K15") (pinfunction "PG3_K15") (pintype "bidirectional"))
    )
    (net (code "114") (name "unconnected-(U2B-PG4-PadK14)") (class "Default")
      (node (ref "U2") (pin "K14") (pinfunction "PG4_K14") (pintype "bidirectional"))
    )
    (net (code "115") (name "unconnected-(U2B-PG5-PadK13)") (class "Default")
      (node (ref "U2") (pin "K13") (pinfunction "PG5_K13") (pintype "bidirectional"))
    )
    (net (code "116") (name "unconnected-(U2B-PG6-PadJ15)") (class "Default")
      (node (ref "U2") (pin "J15") (pinfunction "PG6_J15") (pintype "bidirectional"))
    )
    (net (code "117") (name "unconnected-(U2B-PG7-PadJ14)") (class "Default")
      (node (ref "U2") (pin "J14") (pinfunction "PG7_J14") (pintype "bidirectional"))
    )
    (net (code "118") (name "unconnected-(U2B-PG8-PadH14)") (class "Default")
      (node (ref "U2") (pin "H14") (pinfunction "PG8_H14") (pintype "bidirectional"))
    )
    (net (code "119") (name "unconnected-(U2B-PG9-PadC10)") (class "Default")
      (node (ref "U2") (pin "C10") (pinfunction "PG9_C10") (pintype "bidirectional"))
    )
    (net (code "120") (name "unconnected-(U2B-PG10-PadB10)") (class "Default")
      (node (ref "U2") (pin "B10") (pinfunction "PG10_B10") (pintype "bidirectional"))
    )
    (net (code "121") (name "unconnected-(U2B-PG11-PadB9)") (class "Default")
      (node (ref "U2") (pin "B9") (pinfunction "PG11_B9") (pintype "bidirectional"))
    )
    (net (code "122") (name "unconnected-(U2B-PG12-PadB8)") (class "Default")
      (node (ref "U2") (pin "B8") (pinfunction "PG12_B8") (pintype "bidirectional"))
    )
    (net (code "123") (name "unconnected-(U2B-PG13-PadA8)") (class "Default")
      (node (ref "U2") (pin "A8") (pinfunction "PG13_A8") (pintype "bidirectional"))
    )
    (net (code "124") (name "unconnected-(U2B-PG14-PadA7)") (class "Default")
      (node (ref "U2") (pin "A7") (pinfunction "PG14_A7") (pintype "bidirectional"))
    )
    (net (code "125") (name "unconnected-(U2B-PG15-PadB7)") (class "Default")
      (node (ref "U2") (pin "B7") (pinfunction "PG15_B7") (pintype "bidirectional"))
    )
    (net (code "126") (name "unconnected-(U2B-PH2-PadF4)") (class "Default")
      (node (ref "U2") (pin "F4") (pinfunction "PH2_F4") (pintype "bidirectional"))
    )
    (net (code "127") (name "unconnected-(U2B-PH3-PadG4)") (class "Default")
      (node (ref "U2") (pin "G4") (pinfunction "PH3_G4") (pintype "bidirectional"))
    )
    (net (code "128") (name "unconnected-(U2B-PH4-PadH4)") (class "Default")
      (node (ref "U2") (pin "H4") (pinfunction "PH4_H4") (pintype "bidirectional"))
    )
    (net (code "129") (name "unconnected-(U2B-PH5-PadJ4)") (class "Default")
      (node (ref "U2") (pin "J4") (pinfunction "PH5_J4") (pintype "bidirectional"))
    )
    (net (code "130") (name "unconnected-(U2B-PH6-PadM11)") (class "Default")
      (node (ref "U2") (pin "M11") (pinfunction "PH6_M11") (pintype "bidirectional"))
    )
    (net (code "131") (name "unconnected-(U2B-PH7-PadN12)") (class "Default")
      (node (ref "U2") (pin "N12") (pinfunction "PH7_N12") (pintype "bidirectional"))
    )
    (net (code "132") (name "unconnected-(U2B-PH8-PadM12)") (class "Default")
      (node (ref "U2") (pin "M12") (pinfunction "PH8_M12") (pintype "bidirectional"))
    )
    (net (code "133") (name "unconnected-(U2B-PH9-PadM13)") (class "Default")
      (node (ref "U2") (pin "M13") (pinfunction "PH9_M13") (pintype "bidirectional"))
    )
    (net (code "134") (name "unconnected-(U2B-PH10-PadL13)") (class "Default")
      (node (ref "U2") (pin "L13") (pinfunction "PH10_L13") (pintype "bidirectional"))
    )
    (net (code "135") (name "unconnected-(U2B-PH11-PadL12)") (class "Default")
      (node (ref "U2") (pin "L12") (pinfunction "PH11_L12") (pintype "bidirectional"))
    )
    (net (code "136") (name "unconnected-(U2B-PH12-PadK12)") (class "Default")
      (node (ref "U2") (pin "K12") (pinfunction "PH12_K12") (pintype "bidirectional"))
    )
    (net (code "137") (name "unconnected-(U2B-PH13-PadE12)") (class "Default")
      (node (ref "U2") (pin "E12") (pinfunction "PH13_E12") (pintype "bidirectional"))
    )
    (net (code "138") (name "unconnected-(U2B-PH14-PadE13)") (class "Default")
      (node (ref "U2") (pin "E13") (pinfunction "PH14_E13") (pintype "bidirectional"))
    )
    (net (code "139") (name "unconnected-(U2B-PH15-PadD13)") (class "Default")
      (node (ref "U2") (pin "D13") (pinfunction "PH15_D13") (pintype "bidirectional"))
    )
    (net (code "140") (name "unconnected-(U2B-PI0-PadE14)") (class "Default")
      (node (ref "U2") (pin "E14") (pinfunction "PI0_E14") (pintype "bidirectional"))
    )
    (net (code "141") (name "unconnected-(U2B-PI1-PadD14)") (class "Default")
      (node (ref "U2") (pin "D14") (pinfunction "PI1_D14") (pintype "bidirectional"))
    )
    (net (code "142") (name "unconnected-(U2B-PI2-PadC14)") (class "Default")
      (node (ref "U2") (pin "C14") (pinfunction "PI2_C14") (pintype "bidirectional"))
    )
    (net (code "143") (name "unconnected-(U2B-PI3-PadC13)") (class "Default")
      (node (ref "U2") (pin "C13") (pinfunction "PI3_C13") (pintype "bidirectional"))
    )
    (net (code "144") (name "unconnected-(U2B-PI4-PadD4)") (class "Default")
      (node (ref "U2") (pin "D4") (pinfunction "PI4_D4") (pintype "bidirectional"))
    )
    (net (code "145") (name "unconnected-(U2B-PI5-PadC4)") (class "Default")
      (node (ref "U2") (pin "C4") (pinfunction "PI5_C4") (pintype "bidirectional"))
    )
    (net (code "146") (name "unconnected-(U2B-PI6-PadC3)") (class "Default")
      (node (ref "U2") (pin "C3") (pinfunction "PI6_C3") (pintype "bidirectional"))
    )
    (net (code "147") (name "unconnected-(U2B-PI7-PadC2)") (class "Default")
      (node (ref "U2") (pin "C2") (pinfunction "PI7_C2") (pintype "bidirectional"))
    )
    (net (code "148") (name "unconnected-(U2B-PI8-PadD2)") (class "Default")
      (node (ref "U2") (pin "D2") (pinfunction "PI8_D2") (pintype "bidirectional"))
    )
    (net (code "149") (name "unconnected-(U2B-PI9-PadD3)") (class "Default")
      (node (ref "U2") (pin "D3") (pinfunction "PI9_D3") (pintype "bidirectional"))
    )
    (net (code "150") (name "unconnected-(U2B-PI10-PadE3)") (class "Default")
      (node (ref "U2") (pin "E3") (pinfunction "PI10_E3") (pintype "bidirectional"))
    )
    (net (code "151") (name "unconnected-(U2B-PI11-PadE4)") (class "Default")
      (node (ref "U2") (pin "E4") (pinfunction "PI11_E4") (pintype "bidirectional"))
    )
  )
)
